# Interposer.net
KiCad netlist of a schematic drawn in Altium Designer
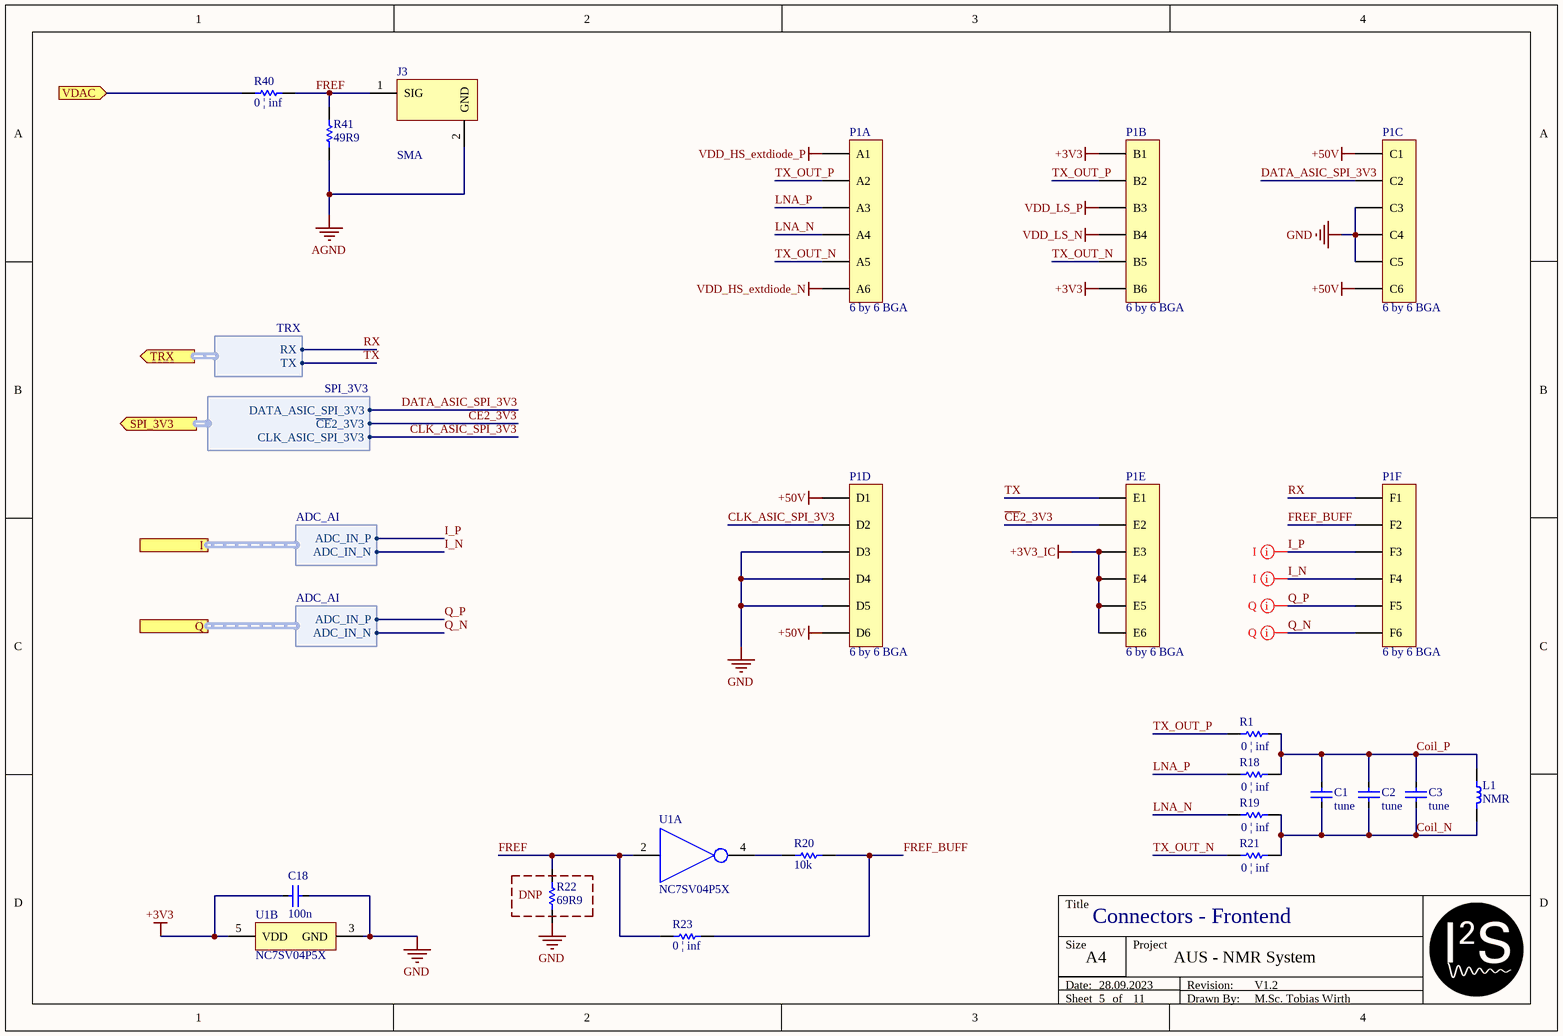
[diagram p0: Interposer.SchDoc]

(export (version "E")
  (design (tool "Eeschema 10.0.6"))
  (components
    (comp (ref "C1") (value "tune") (footprint "CAP_1206") (libsource (lib "IIS-Lib_TW") (part "Cap")))
    (comp (ref "C2") (value "tune") (footprint "CAP_0805") (libsource (lib "IIS-Lib_TW") (part "Cap")))
    (comp (ref "C3") (value "tune") (footprint "CAP_0603") (libsource (lib "IIS-Lib_TW") (part "Cap")))
    (comp (ref "C18") (value "100n") (footprint "CAP_0402") (libsource (lib "IIS-Lib_TW") (part "Cap")))
    (comp (ref "J3") (value "SMA") (footprint "SMA") (libsource (lib "IIS-Lib_TW") (part "SMA")))
    (comp (ref "L1") (value "NMR") (footprint "NMR-Coil-Pads") (libsource (lib "IIS-Lib_TW") (part "Ind")))
    (comp (ref "P1")
      (value "6 by 6 BGA")
      (footprint "BGA36C230P6X6_1500X1500X190 - Interposer")
      (libsource (lib "IIS-Lib_TW") (part "BGA_6x6"))
    )
    (comp (ref "R1") (value "0 ¦ inf") (footprint "RES_0402") (libsource (lib "IIS-Lib_TW") (part "Res")))
    (comp (ref "R18") (value "0 ¦ inf") (footprint "RES_0402") (libsource (lib "IIS-Lib_TW") (part "Res")))
    (comp (ref "R19") (value "0 ¦ inf") (footprint "RES_0402") (libsource (lib "IIS-Lib_TW") (part "Res")))
    (comp (ref "R20") (value "10k") (footprint "RES_0402") (libsource (lib "IIS-Lib_TW") (part "Res")))
    (comp (ref "R21") (value "0 ¦ inf") (footprint "RES_0402") (libsource (lib "IIS-Lib_TW") (part "Res")))
    (comp (ref "R22") (value "69R9") (footprint "RES_0603") (libsource (lib "IIS-Lib_TW") (part "Res")))
    (comp (ref "R23") (value "0 ¦ inf") (footprint "RES_0402") (libsource (lib "IIS-Lib_TW") (part "Res")))
    (comp (ref "R40") (value "0 ¦ inf") (footprint "RES_0402") (libsource (lib "IIS-Lib_TW") (part "Res")))
    (comp (ref "R41") (value "49R9") (footprint "RES_0402") (libsource (lib "IIS-Lib_TW") (part "Res")))
    (comp (ref "U1")
      (value "NC7SV04P5X")
      (footprint "SOT23-65P210X110-5N")
      (libsource (lib "") (part "NC7SV04P5X_1"))
    )
  )
  (nets
    (net (code "4") (name "+3V3") (class "Default")
      (node (ref "C18") (pin "1") (pinfunction "1_1") (pintype "passive"))
      (node (ref "P1") (pin "B1") (pinfunction "B1_B1") (pintype "passive"))
      (node (ref "P1") (pin "B6") (pinfunction "B6_B6") (pintype "passive"))
      (node (ref "U1") (pin "5") (pinfunction "VDD_5") (pintype "passive"))
    )
    (net (code "5") (name "+3V3_IC") (class "Default")
      (node (ref "P1") (pin "E3") (pinfunction "E3_E3") (pintype "passive"))
      (node (ref "P1") (pin "E4") (pinfunction "E4_E4") (pintype "passive"))
      (node (ref "P1") (pin "E5") (pinfunction "E5_E5") (pintype "passive"))
      (node (ref "P1") (pin "E6") (pinfunction "E6_E6") (pintype "passive"))
    )
    (net (code "6") (name "+50V") (class "Default")
      (node (ref "P1") (pin "C1") (pinfunction "C1_C1") (pintype "passive"))
      (node (ref "P1") (pin "C6") (pinfunction "C6_C6") (pintype "passive"))
      (node (ref "P1") (pin "D1") (pinfunction "D1_D1") (pintype "passive"))
      (node (ref "P1") (pin "D6") (pinfunction "D6_D6") (pintype "passive"))
    )
    (net (code "7") (name "/CLK_ASIC_SPI_3V3") (class "Default")
      (node (ref "P1") (pin "D2") (pinfunction "D2_D2") (pintype "passive"))
    )
    (net (code "8") (name "/Coil_N") (class "Default")
      (node (ref "C1") (pin "2") (pinfunction "2_2") (pintype "passive"))
      (node (ref "C2") (pin "2") (pinfunction "2_2") (pintype "passive"))
      (node (ref "C3") (pin "2") (pinfunction "2_2") (pintype "passive"))
      (node (ref "L1") (pin "2") (pinfunction "2_2") (pintype "passive"))
      (node (ref "R19") (pin "1") (pinfunction "1_1") (pintype "passive"))
      (node (ref "R21") (pin "1") (pinfunction "1_1") (pintype "passive"))
    )
    (net (code "9") (name "/Coil_P") (class "Default")
      (node (ref "C1") (pin "1") (pinfunction "1_1") (pintype "passive"))
      (node (ref "C2") (pin "1") (pinfunction "1_1") (pintype "passive"))
      (node (ref "C3") (pin "1") (pinfunction "1_1") (pintype "passive"))
      (node (ref "L1") (pin "1") (pinfunction "1_1") (pintype "passive"))
      (node (ref "R1") (pin "1") (pinfunction "1_1") (pintype "passive"))
      (node (ref "R18") (pin "1") (pinfunction "1_1") (pintype "passive"))
    )
    (net (code "10") (name "/DATA_ASIC_SPI_3V3") (class "Default")
      (node (ref "P1") (pin "C2") (pinfunction "C2_C2") (pintype "passive"))
    )
    (net (code "11") (name "/FREF") (class "Default")
      (node (ref "J3") (pin "1") (pinfunction "SIG_1") (pintype "passive"))
      (node (ref "R22") (pin "2") (pinfunction "2_2") (pintype "passive"))
      (node (ref "R23") (pin "2") (pinfunction "2_2") (pintype "passive"))
      (node (ref "R40") (pin "2") (pinfunction "2_2") (pintype "passive"))
      (node (ref "R41") (pin "2") (pinfunction "2_2") (pintype "passive"))
      (node (ref "U1") (pin "2") (pinfunction "2_2") (pintype "passive"))
    )
    (net (code "12") (name "/FREF_BUFF") (class "Default")
      (node (ref "P1") (pin "F2") (pinfunction "F2_F2") (pintype "passive"))
      (node (ref "R20") (pin "2") (pinfunction "2_2") (pintype "passive"))
      (node (ref "R23") (pin "1") (pinfunction "1_1") (pintype "passive"))
    )
    (net (code "13") (name "/I_N") (class "Default")
      (node (ref "P1") (pin "F4") (pinfunction "F4_F4") (pintype "passive"))
    )
    (net (code "14") (name "/I_P") (class "Default")
      (node (ref "P1") (pin "F3") (pinfunction "F3_F3") (pintype "passive"))
    )
    (net (code "15") (name "/LNA_N") (class "Default")
      (node (ref "P1") (pin "A4") (pinfunction "A4_A4") (pintype "passive"))
      (node (ref "R19") (pin "2") (pinfunction "2_2") (pintype "passive"))
    )
    (net (code "16") (name "/LNA_P") (class "Default")
      (node (ref "P1") (pin "A3") (pinfunction "A3_A3") (pintype "passive"))
      (node (ref "R18") (pin "2") (pinfunction "2_2") (pintype "passive"))
    )
    (net (code "17") (name "/Q_N") (class "Default")
      (node (ref "P1") (pin "F6") (pinfunction "F6_F6") (pintype "passive"))
    )
    (net (code "18") (name "/Q_P") (class "Default")
      (node (ref "P1") (pin "F5") (pinfunction "F5_F5") (pintype "passive"))
    )
    (net (code "19") (name "/RX") (class "Default")
      (node (ref "P1") (pin "F1") (pinfunction "F1_F1") (pintype "passive"))
    )
    (net (code "20") (name "/TX") (class "Default")
      (node (ref "P1") (pin "E1") (pinfunction "E1_E1") (pintype "passive"))
    )
    (net (code "21") (name "/TX_OUT_N") (class "Default")
      (node (ref "P1") (pin "A5") (pinfunction "A5_A5") (pintype "passive"))
      (node (ref "P1") (pin "B5") (pinfunction "B5_B5") (pintype "passive"))
      (node (ref "R21") (pin "2") (pinfunction "2_2") (pintype "passive"))
    )
    (net (code "22") (name "/TX_OUT_P") (class "Default")
      (node (ref "P1") (pin "A2") (pinfunction "A2_A2") (pintype "passive"))
      (node (ref "P1") (pin "B2") (pinfunction "B2_B2") (pintype "passive"))
      (node (ref "R1") (pin "2") (pinfunction "2_2") (pintype "passive"))
    )
    (net (code "23") (name "/VDAC") (class "Default")
      (node (ref "R40") (pin "1") (pinfunction "1_1") (pintype "passive"))
    )
    (net (code "27") (name "/~{CE}2_3V3") (class "Default")
      (node (ref "P1") (pin "E2") (pinfunction "E2_E2") (pintype "passive"))
    )
    (net (code "28") (name "AGND") (class "Default")
      (node (ref "J3") (pin "2") (pinfunction "GND_2") (pintype "passive"))
      (node (ref "R41") (pin "1") (pinfunction "1_1") (pintype "passive"))
    )
    (net (code "29") (name "GND") (class "Default")
      (node (ref "C18") (pin "2") (pinfunction "2_2") (pintype "passive"))
      (node (ref "P1") (pin "C3") (pinfunction "C3_C3") (pintype "passive"))
      (node (ref "P1") (pin "C4") (pinfunction "C4_C4") (pintype "passive"))
      (node (ref "P1") (pin "C5") (pinfunction "C5_C5") (pintype "passive"))
      (node (ref "P1") (pin "D3") (pinfunction "D3_D3") (pintype "passive"))
      (node (ref "P1") (pin "D4") (pinfunction "D4_D4") (pintype "passive"))
      (node (ref "P1") (pin "D5") (pinfunction "D5_D5") (pintype "passive"))
      (node (ref "R22") (pin "1") (pinfunction "1_1") (pintype "passive"))
      (node (ref "U1") (pin "3") (pinfunction "GND_3") (pintype "passive"))
    )
    (net (code "30") (name "Net-(R20-Pad1)") (class "Default")
      (node (ref "R20") (pin "1") (pinfunction "1_1") (pintype "passive"))
      (node (ref "U1") (pin "4") (pinfunction "4_4") (pintype "passive"))
    )
    (net (code "31") (name "VDD_HS_extdiode_N") (class "Default")
      (node (ref "P1") (pin "A6") (pinfunction "A6_A6") (pintype "passive"))
    )
    (net (code "32") (name "VDD_HS_extdiode_P") (class "Default")
      (node (ref "P1") (pin "A1") (pinfunction "A1_A1") (pintype "passive"))
    )
    (net (code "33") (name "VDD_LS_N") (class "Default")
      (node (ref "P1") (pin "B4") (pinfunction "B4_B4") (pintype "passive"))
    )
    (net (code "34") (name "VDD_LS_P") (class "Default")
      (node (ref "P1") (pin "B3") (pinfunction "B3_B3") (pintype "passive"))
    )
  )
)
